# RGB_LED.net
KiCad netlist of a schematic drawn in Altium Designer
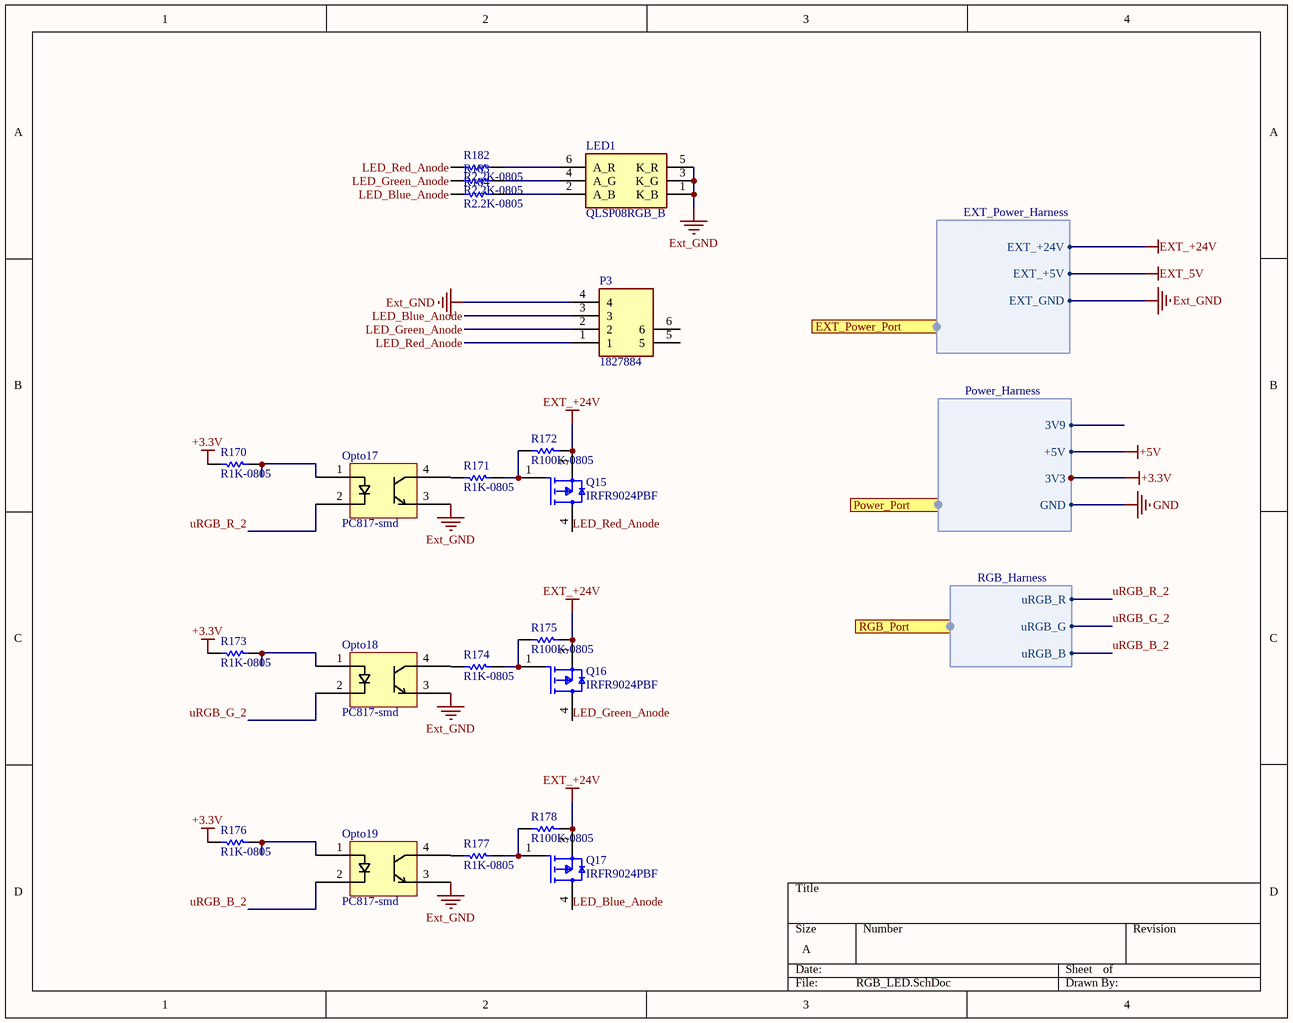
[diagram p0: RGB_LED.SchDoc]

(export (version "E")
  (design (tool "Eeschema 10.0.6"))
  (components
    (comp (ref "LED1")
      (value "QLSP08RGB_B")
      (footprint "SamacSys:QLSP08RGB_B")
      (description "LED")
      (fields (field (name "DIGI-KEY_PART_NUMBER") "3970-QLSP08RGB_BTR-ND"))
      (libsource (lib "*") (part "QLSP08RGB_B"))
    )
    (comp (ref "Opto17")
      (value "PC817-smd")
      (footprint "PC817_SMD1")
      (fields (field (name "DIGI-KEY_PART_NUMBER") "2007-APC-817D1-SLTR-ND"))
      (libsource (lib "Almas Co") (part "PC817"))
    )
    (comp (ref "Opto18")
      (value "PC817-smd")
      (footprint "PC817_SMD1")
      (fields (field (name "DIGI-KEY_PART_NUMBER") "2007-APC-817D1-SLTR-ND"))
      (libsource (lib "Almas Co") (part "PC817"))
    )
    (comp (ref "Opto19")
      (value "PC817-smd")
      (footprint "PC817_SMD1")
      (fields (field (name "DIGI-KEY_PART_NUMBER") "2007-APC-817D1-SLTR-ND"))
      (libsource (lib "Almas Co") (part "PC817"))
    )
    (comp (ref "P3")
      (value "1827884")
      (footprint "SamacSys:1827884")
      (description "Connector")
      (fields
        (field (name "MOUSER PART NUMBER") "651-1827884")
        (field (name "DIGI-KEY_PART_NUMBER") "277-5791-ND")
      )
      (libsource (lib "*") (part "1827884"))
    )
    (comp (ref "Q15")
      (value "IRFR9024PBF")
      (footprint "FP-E22-0399-N-MFG")
      (description "MOSFET P-CH 60V 8.8A DPAK")
      (fields (field (name "DIGI-KEY_PART_NUMBER") "IRFR9024PBF-ND"))
      (libsource (lib "Altium Content Vault") (part "398b9b0ec8084fdfbb5a636f7f7ede9"))
    )
    (comp (ref "Q16")
      (value "IRFR9024PBF")
      (footprint "FP-E22-0399-N-MFG")
      (description "MOSFET P-CH 60V 8.8A DPAK")
      (fields (field (name "DIGI-KEY_PART_NUMBER") "IRFR9024PBF-ND"))
      (libsource (lib "Altium Content Vault") (part "398b9b0ec8084fdfbb5a636f7f7ede9"))
    )
    (comp (ref "Q17")
      (value "IRFR9024PBF")
      (footprint "FP-E22-0399-N-MFG")
      (description "MOSFET P-CH 60V 8.8A DPAK")
      (fields (field (name "DIGI-KEY_PART_NUMBER") "IRFR9024PBF-ND"))
      (libsource (lib "Altium Content Vault") (part "398b9b0ec8084fdfbb5a636f7f7ede9"))
    )
    (comp (ref "R170")
      (value "R1K-0805")
      (footprint "CRF06031")
      (description "Resistor")
      (fields (field (name "DIGI-KEY_PART_NUMBER") "311-1.00KCRTR-ND"))
      (libsource (lib "Miscellaneous Devices") (part "Res1"))
    )
    (comp (ref "R171")
      (value "R1K-0805")
      (footprint "CRF06031")
      (description "Resistor")
      (fields (field (name "DIGI-KEY_PART_NUMBER") "311-1.00KCRTR-ND"))
      (libsource (lib "Miscellaneous Devices") (part "Res1"))
    )
    (comp (ref "R172")
      (value "R100K-0805")
      (footprint "CRF06031")
      (description "Resistor")
      (fields (field (name "DIGI-KEY_PART_NUMBER") "311-100KCRTR-ND"))
      (libsource (lib "Miscellaneous Devices") (part "Res1"))
    )
    (comp (ref "R173")
      (value "R1K-0805")
      (footprint "CRF06031")
      (description "Resistor")
      (fields (field (name "DIGI-KEY_PART_NUMBER") "311-1.00KCRTR-ND"))
      (libsource (lib "Miscellaneous Devices") (part "Res1"))
    )
    (comp (ref "R174")
      (value "R1K-0805")
      (footprint "CRF06031")
      (description "Resistor")
      (fields (field (name "DIGI-KEY_PART_NUMBER") "311-1.00KCRTR-ND"))
      (libsource (lib "Miscellaneous Devices") (part "Res1"))
    )
    (comp (ref "R175")
      (value "R100K-0805")
      (footprint "CRF06031")
      (description "Resistor")
      (fields (field (name "DIGI-KEY_PART_NUMBER") "311-100KCRTR-ND"))
      (libsource (lib "Miscellaneous Devices") (part "Res1"))
    )
    (comp (ref "R176")
      (value "R1K-0805")
      (footprint "CRF06031")
      (description "Resistor")
      (fields (field (name "DIGI-KEY_PART_NUMBER") "311-1.00KCRTR-ND"))
      (libsource (lib "Miscellaneous Devices") (part "Res1"))
    )
    (comp (ref "R177")
      (value "R1K-0805")
      (footprint "CRF06031")
      (description "Resistor")
      (fields (field (name "DIGI-KEY_PART_NUMBER") "311-1.00KCRTR-ND"))
      (libsource (lib "Miscellaneous Devices") (part "Res1"))
    )
    (comp (ref "R178")
      (value "R100K-0805")
      (footprint "CRF06031")
      (description "Resistor")
      (fields (field (name "DIGI-KEY_PART_NUMBER") "311-100KCRTR-ND"))
      (libsource (lib "Miscellaneous Devices") (part "Res1"))
    )
    (comp (ref "R182")
      (value "R2.2K-0805")
      (footprint "CRF06031")
      (description "Resistor")
      (fields (field (name "DIGI-KEY_PART_NUMBER") "311-2.20KCRTR-ND"))
      (libsource (lib "Miscellaneous Devices") (part "Res1"))
    )
    (comp (ref "R183")
      (value "R2.2K-0805")
      (footprint "CRF06031")
      (description "Resistor")
      (fields (field (name "DIGI-KEY_PART_NUMBER") "311-2.20KCRTR-ND"))
      (libsource (lib "Miscellaneous Devices") (part "Res1"))
    )
    (comp (ref "R184")
      (value "R2.2K-0805")
      (footprint "CRF06031")
      (description "Resistor")
      (fields (field (name "DIGI-KEY_PART_NUMBER") "311-2.20KCRTR-ND"))
      (libsource (lib "Miscellaneous Devices") (part "Res1"))
    )
  )
  (nets
    (net (code "4") (name "+3.3V") (class "Default")
      (node (ref "R170") (pin "2") (pinfunction "2_2") (pintype "passive"))
      (node (ref "R173") (pin "2") (pinfunction "2_2") (pintype "passive"))
      (node (ref "R176") (pin "2") (pinfunction "2_2") (pintype "passive"))
    )
    (net (code "6") (name "/LED_Blue_Anode") (class "Default")
      (node (ref "P3") (pin "3") (pinfunction "3_3") (pintype "passive"))
      (node (ref "Q17") (pin "4") (pinfunction "D_4") (pintype "passive"))
      (node (ref "R184") (pin "1") (pinfunction "1_1") (pintype "passive"))
    )
    (net (code "7") (name "/LED_Green_Anode") (class "Default")
      (node (ref "P3") (pin "2") (pinfunction "2_2") (pintype "passive"))
      (node (ref "Q16") (pin "4") (pinfunction "D_4") (pintype "passive"))
      (node (ref "R183") (pin "1") (pinfunction "1_1") (pintype "passive"))
    )
    (net (code "8") (name "/LED_Red_Anode") (class "Default")
      (node (ref "P3") (pin "1") (pinfunction "1_1") (pintype "passive"))
      (node (ref "Q15") (pin "4") (pinfunction "D_4") (pintype "passive"))
      (node (ref "R182") (pin "1") (pinfunction "1_1") (pintype "passive"))
    )
    (net (code "9") (name "/uRGB_B_2") (class "Default") (node (ref "Opto19") (pin "2") (pintype "passive")))
    (net (code "10") (name "/uRGB_G_2") (class "Default") (node (ref "Opto18") (pin "2") (pintype "passive")))
    (net (code "11") (name "/uRGB_R_2") (class "Default") (node (ref "Opto17") (pin "2") (pintype "passive")))
    (net (code "15") (name "EXT_+24V") (class "Default")
      (node (ref "Q15") (pin "3") (pinfunction "S_3") (pintype "passive"))
      (node (ref "Q16") (pin "3") (pinfunction "S_3") (pintype "passive"))
      (node (ref "Q17") (pin "3") (pinfunction "S_3") (pintype "passive"))
      (node (ref "R172") (pin "2") (pinfunction "2_2") (pintype "passive"))
      (node (ref "R175") (pin "2") (pinfunction "2_2") (pintype "passive"))
      (node (ref "R178") (pin "2") (pinfunction "2_2") (pintype "passive"))
    )
    (net (code "17") (name "Ext_GND") (class "Default")
      (node (ref "LED1") (pin "1") (pinfunction "K_B_1") (pintype "passive"))
      (node (ref "LED1") (pin "3") (pinfunction "K_G_3") (pintype "passive"))
      (node (ref "LED1") (pin "5") (pinfunction "K_R_5") (pintype "passive"))
      (node (ref "Opto17") (pin "3") (pintype "passive"))
      (node (ref "Opto18") (pin "3") (pintype "passive"))
      (node (ref "Opto19") (pin "3") (pintype "passive"))
      (node (ref "P3") (pin "4") (pinfunction "4_4") (pintype "passive"))
    )
    (net (code "19") (name "Net-(LED1-A_B)") (class "Default")
      (node (ref "LED1") (pin "2") (pinfunction "A_B_2") (pintype "passive"))
      (node (ref "R184") (pin "2") (pinfunction "2_2") (pintype "passive"))
    )
    (net (code "20") (name "Net-(LED1-A_G)") (class "Default")
      (node (ref "LED1") (pin "4") (pinfunction "A_G_4") (pintype "passive"))
      (node (ref "R183") (pin "2") (pinfunction "2_2") (pintype "passive"))
    )
    (net (code "21") (name "Net-(LED1-A_R)") (class "Default")
      (node (ref "LED1") (pin "6") (pinfunction "A_R_6") (pintype "passive"))
      (node (ref "R182") (pin "2") (pinfunction "2_2") (pintype "passive"))
    )
    (net (code "22") (name "Net-(Opto17-Pad1)") (class "Default")
      (node (ref "Opto17") (pin "1") (pintype "passive"))
      (node (ref "R170") (pin "1") (pinfunction "1_1") (pintype "passive"))
    )
    (net (code "23") (name "Net-(Opto17-Pad4)") (class "Default")
      (node (ref "Opto17") (pin "4") (pintype "passive"))
      (node (ref "R171") (pin "2") (pinfunction "2_2") (pintype "passive"))
    )
    (net (code "24") (name "Net-(Opto18-Pad1)") (class "Default")
      (node (ref "Opto18") (pin "1") (pintype "passive"))
      (node (ref "R173") (pin "1") (pinfunction "1_1") (pintype "passive"))
    )
    (net (code "25") (name "Net-(Opto18-Pad4)") (class "Default")
      (node (ref "Opto18") (pin "4") (pintype "passive"))
      (node (ref "R174") (pin "2") (pinfunction "2_2") (pintype "passive"))
    )
    (net (code "26") (name "Net-(Opto19-Pad1)") (class "Default")
      (node (ref "Opto19") (pin "1") (pintype "passive"))
      (node (ref "R176") (pin "1") (pinfunction "1_1") (pintype "passive"))
    )
    (net (code "27") (name "Net-(Opto19-Pad4)") (class "Default")
      (node (ref "Opto19") (pin "4") (pintype "passive"))
      (node (ref "R177") (pin "2") (pinfunction "2_2") (pintype "passive"))
    )
    (net (code "28") (name "Net-(Q15-G)") (class "Default")
      (node (ref "Q15") (pin "1") (pinfunction "G_1") (pintype "passive"))
      (node (ref "R171") (pin "1") (pinfunction "1_1") (pintype "passive"))
      (node (ref "R172") (pin "1") (pinfunction "1_1") (pintype "passive"))
    )
    (net (code "29") (name "Net-(Q16-G)") (class "Default")
      (node (ref "Q16") (pin "1") (pinfunction "G_1") (pintype "passive"))
      (node (ref "R174") (pin "1") (pinfunction "1_1") (pintype "passive"))
      (node (ref "R175") (pin "1") (pinfunction "1_1") (pintype "passive"))
    )
    (net (code "30") (name "Net-(Q17-G)") (class "Default")
      (node (ref "Q17") (pin "1") (pinfunction "G_1") (pintype "passive"))
      (node (ref "R177") (pin "1") (pinfunction "1_1") (pintype "passive"))
      (node (ref "R178") (pin "1") (pinfunction "1_1") (pintype "passive"))
    )
    (net (code "31") (name "unconnected-(P3-Pad5)") (class "Default")
      (node (ref "P3") (pin "5") (pinfunction "5_5") (pintype "passive"))
    )
    (net (code "32") (name "unconnected-(P3-Pad6)") (class "Default")
      (node (ref "P3") (pin "6") (pinfunction "6_6") (pintype "passive"))
    )
  )
)
